# Power_Breakouts.net
KiCad netlist of a schematic drawn in EAGLE
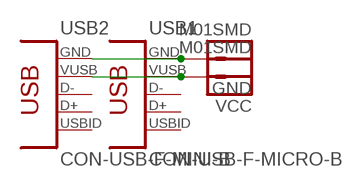
[diagram p0: schematic, sheet 1]

(export (version "E")
  (design (tool "Eeschema 10.0.6"))
  (components
    (comp (ref "GND")
      (value "M01SMD")
      (footprint "eagle-import:LUXEON-PAD")
      (libsource (lib "eagle-import") (part "M01SMD"))
    )
    (comp (ref "USB1")
      (value "CON-USB-F-MICRO-B")
      (footprint "eagle-import:CONN_USB_MICRO-B")
      (libsource (lib "eagle-import") (part "CON-USB-F-MICRO-B"))
    )
    (comp (ref "USB2")
      (value "CON-USB-F-MINI-B")
      (footprint "eagle-import:CONN_USB_MINI-B")
      (libsource (lib "eagle-import") (part "CON-USB-F-MINI-B"))
    )
    (comp (ref "VCC")
      (value "M01SMD")
      (footprint "eagle-import:LUXEON-PAD")
      (libsource (lib "eagle-import") (part "M01SMD"))
    )
  )
  (nets
    (net (code "1") (name "Net-(GND-1)") (class "Default")
      (node (ref "GND") (pin "P$1") (pinfunction "1_P$1") (pintype "passive"))
      (node (ref "USB1") (pin "P5") (pinfunction "GND_P5") (pintype "bidirectional"))
      (node (ref "USB2") (pin "GND") (pinfunction "GND_GND") (pintype "bidirectional"))
    )
    (net (code "2") (name "Net-(USB1B-VUSB)") (class "Default")
      (node (ref "USB1") (pin "P1") (pinfunction "VUSB_P1") (pintype "bidirectional"))
      (node (ref "USB2") (pin "VUSB") (pinfunction "VUSB_VUSB") (pintype "bidirectional"))
      (node (ref "VCC") (pin "P$1") (pinfunction "1_P$1") (pintype "passive"))
    )
    (net (code "3") (name "unconnected-(USB1B-D+-PadP3)") (class "Default")
      (node (ref "USB1") (pin "P3") (pinfunction "D+_P3") (pintype "bidirectional"))
    )
    (net (code "4") (name "unconnected-(USB1B-D--PadP2)") (class "Default")
      (node (ref "USB1") (pin "P2") (pinfunction "D-_P2") (pintype "bidirectional"))
    )
    (net (code "5") (name "unconnected-(USB1B-USBID-PadP4)") (class "Default")
      (node (ref "USB1") (pin "P4") (pinfunction "USBID_P4") (pintype "bidirectional"))
    )
    (net (code "6") (name "unconnected-(USB2-PadD+)") (class "Default")
      (node (ref "USB2") (pin "D+") (pinfunction "D+_D+") (pintype "bidirectional"))
    )
    (net (code "7") (name "unconnected-(USB2-PadD-)") (class "Default")
      (node (ref "USB2") (pin "D-") (pinfunction "D-_D-") (pintype "bidirectional"))
    )
    (net (code "8") (name "unconnected-(USB2B-USBID-PadID)") (class "Default")
      (node (ref "USB2") (pin "ID") (pinfunction "USBID_ID") (pintype "bidirectional"))
    )
  )
)
